# AST1026.net
KiCad netlist of a schematic drawn in EAGLE
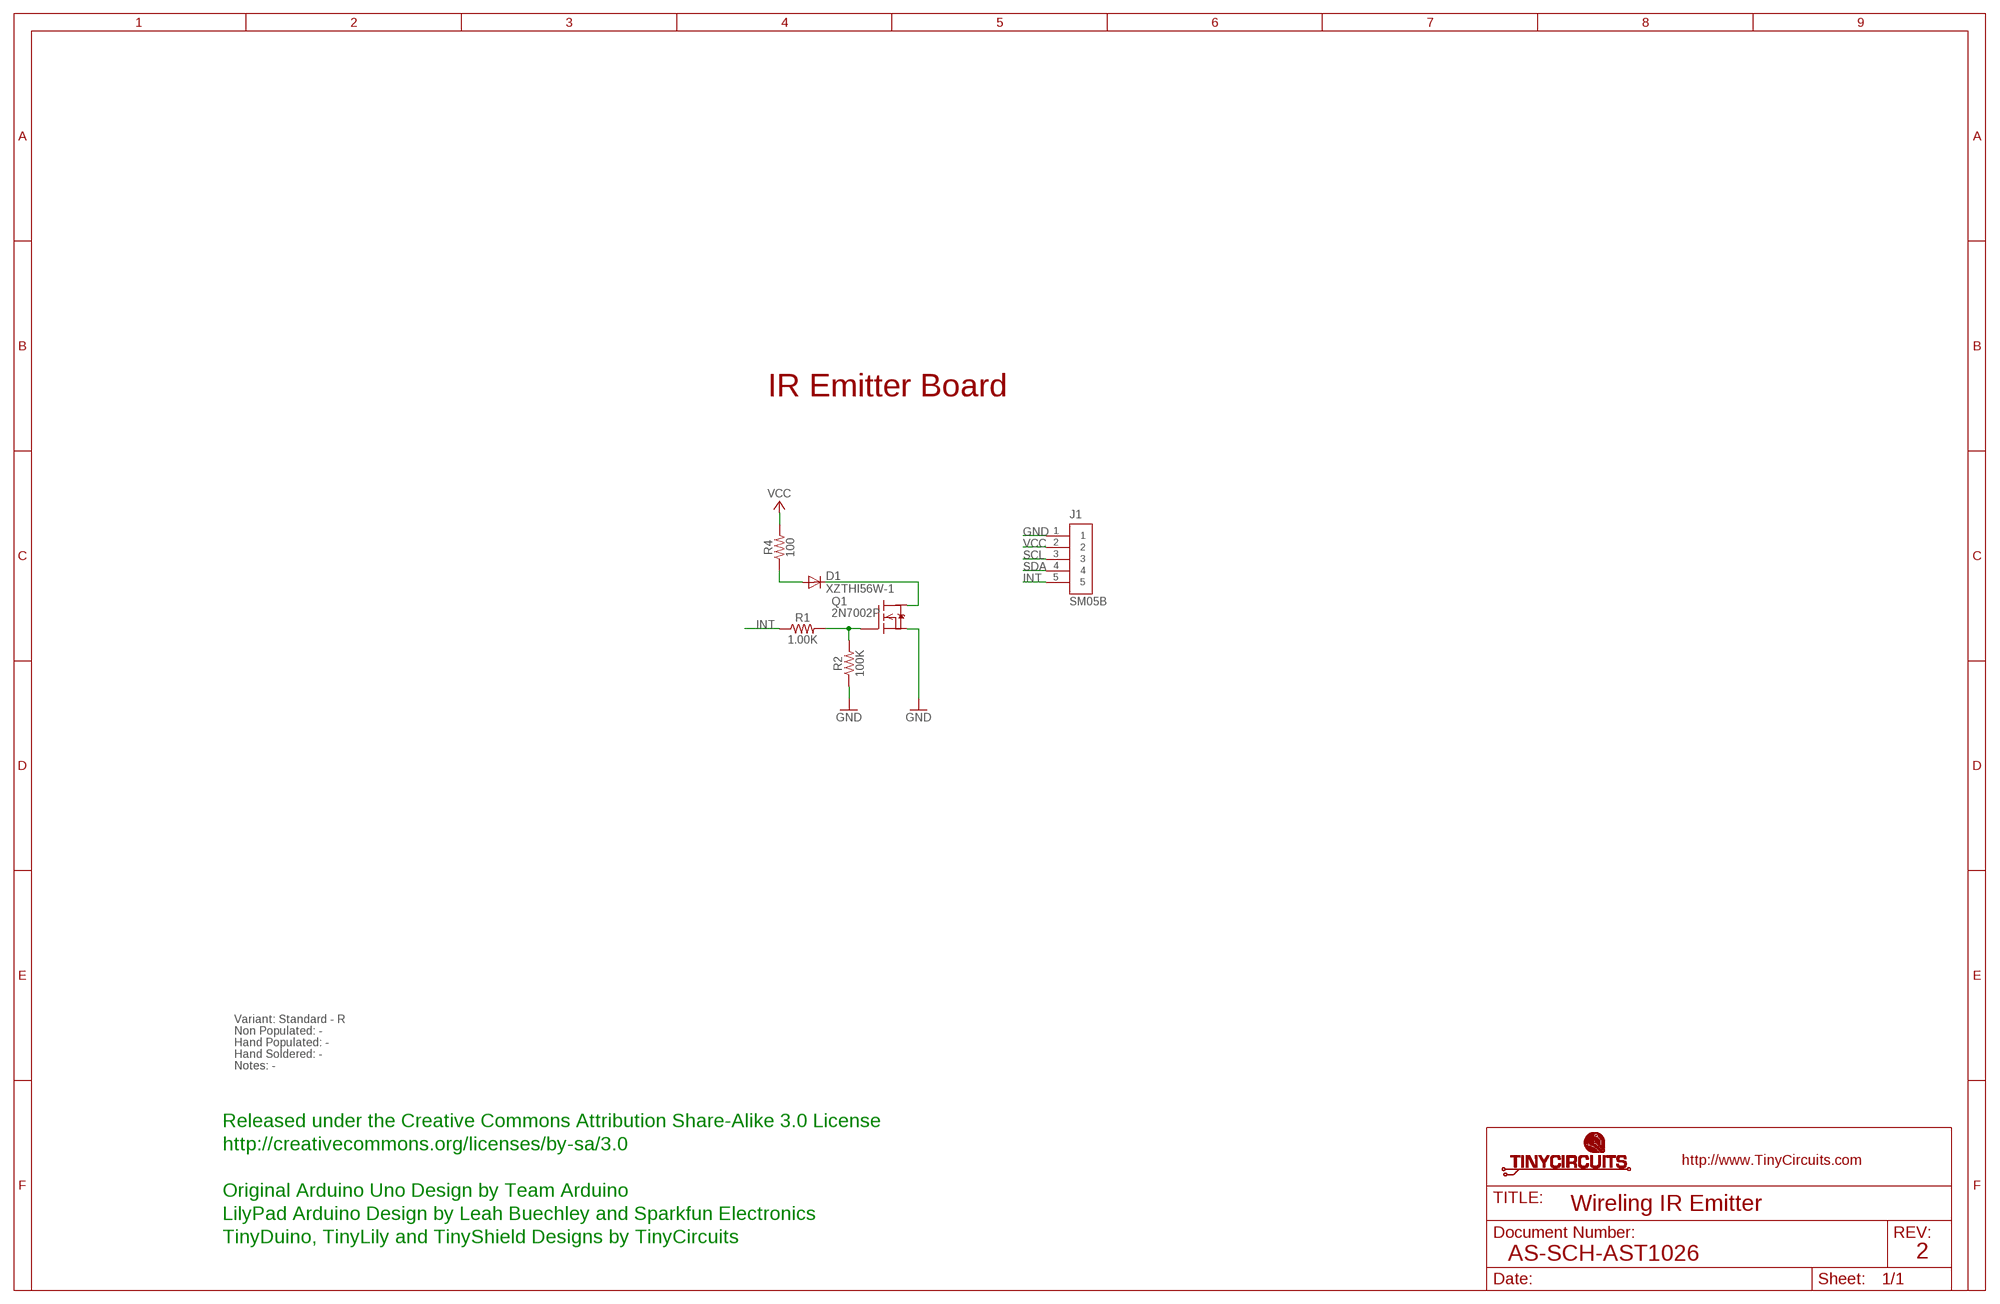
[diagram p0: schematic, sheet 1]

(export (version "E")
  (design (tool "Eeschema 10.0.6"))
  (components
    (comp (ref "D1")
      (value "XZTHI56W-1")
      (footprint "eagle-import:LED_SIDE_3.0X1.0")
      (fields (field (name "PARTNO") "AS-ITM-00551") (field (name "PARTNO_1") "AS-ITM-00551"))
      (libsource (lib "eagle-import") (part "AS-ITM-00551"))
    )
    (comp (ref "J1")
      (value "SM05B")
      (footprint "eagle-import:JST_SH_5X1_EDGE")
      (fields (field (name "PARTNO") "AS-ITM-00340"))
      (libsource (lib "eagle-import") (part "AS-ITM-00340EDGE"))
    )
    (comp (ref "Q1")
      (value "2N7002P")
      (footprint "eagle-import:SOT-416")
      (fields (field (name "PARTNO") "AS-ITM-00110") (field (name "PARTNO_1") "AS-ITM-00110"))
      (libsource (lib "eagle-import") (part "AS-ITM-00110"))
    )
    (comp (ref "R1")
      (value "1.00K")
      (footprint "eagle-import:0402")
      (fields (field (name "PARTNO") "AS-ITM-00003"))
      (libsource (lib "eagle-import") (part "AS-ITM-00003"))
    )
    (comp (ref "R2")
      (value "100K")
      (footprint "eagle-import:0402")
      (fields (field (name "PARTNO") "AS-ITM-00004"))
      (libsource (lib "eagle-import") (part "AS-ITM-00004"))
    )
    (comp (ref "R4")
      (value "100")
      (footprint "eagle-import:0402")
      (fields (field (name "PARTNO") "AS-ITM-0210"))
      (libsource (lib "eagle-import") (part "AS-ITM-00210"))
    )
  )
  (nets
    (net (code "1") (name "/INT") (class "Default")
      (node (ref "J1") (pin "5") (pinfunction "5_5") (pintype "bidirectional"))
      (node (ref "R1") (pin "1") (pinfunction "1_1") (pintype "passive"))
    )
    (net (code "2") (name "/SCL") (class "Default")
      (node (ref "J1") (pin "3") (pinfunction "3_3") (pintype "bidirectional"))
    )
    (net (code "3") (name "/SDA") (class "Default")
      (node (ref "J1") (pin "4") (pinfunction "4_4") (pintype "bidirectional"))
    )
    (net (code "4") (name "GND") (class "Default")
      (node (ref "J1") (pin "1") (pinfunction "1_1") (pintype "bidirectional"))
      (node (ref "Q1") (pin "2") (pinfunction "S_2") (pintype "passive"))
      (node (ref "R2") (pin "1") (pinfunction "1_1") (pintype "passive"))
    )
    (net (code "5") (name "Net-(D1-PadA)") (class "Default")
      (node (ref "D1") (pin "A") (pinfunction "A_A") (pintype "passive"))
      (node (ref "R4") (pin "1") (pinfunction "1_1") (pintype "passive"))
    )
    (net (code "6") (name "Net-(Q1-D)") (class "Default")
      (node (ref "D1") (pin "C") (pinfunction "C_C") (pintype "passive"))
      (node (ref "Q1") (pin "3") (pinfunction "D_3") (pintype "passive"))
    )
    (net (code "7") (name "Net-(Q1-G)") (class "Default")
      (node (ref "Q1") (pin "1") (pinfunction "G_1") (pintype "passive"))
      (node (ref "R1") (pin "2") (pinfunction "2_2") (pintype "passive"))
      (node (ref "R2") (pin "2") (pinfunction "2_2") (pintype "passive"))
    )
    (net (code "8") (name "VCC") (class "Default")
      (node (ref "J1") (pin "2") (pinfunction "2_2") (pintype "bidirectional"))
      (node (ref "R4") (pin "2") (pinfunction "2_2") (pintype "passive"))
    )
  )
)
